# Input_circuits_Page_1.net
KiCad netlist of a schematic drawn in Altium Designer
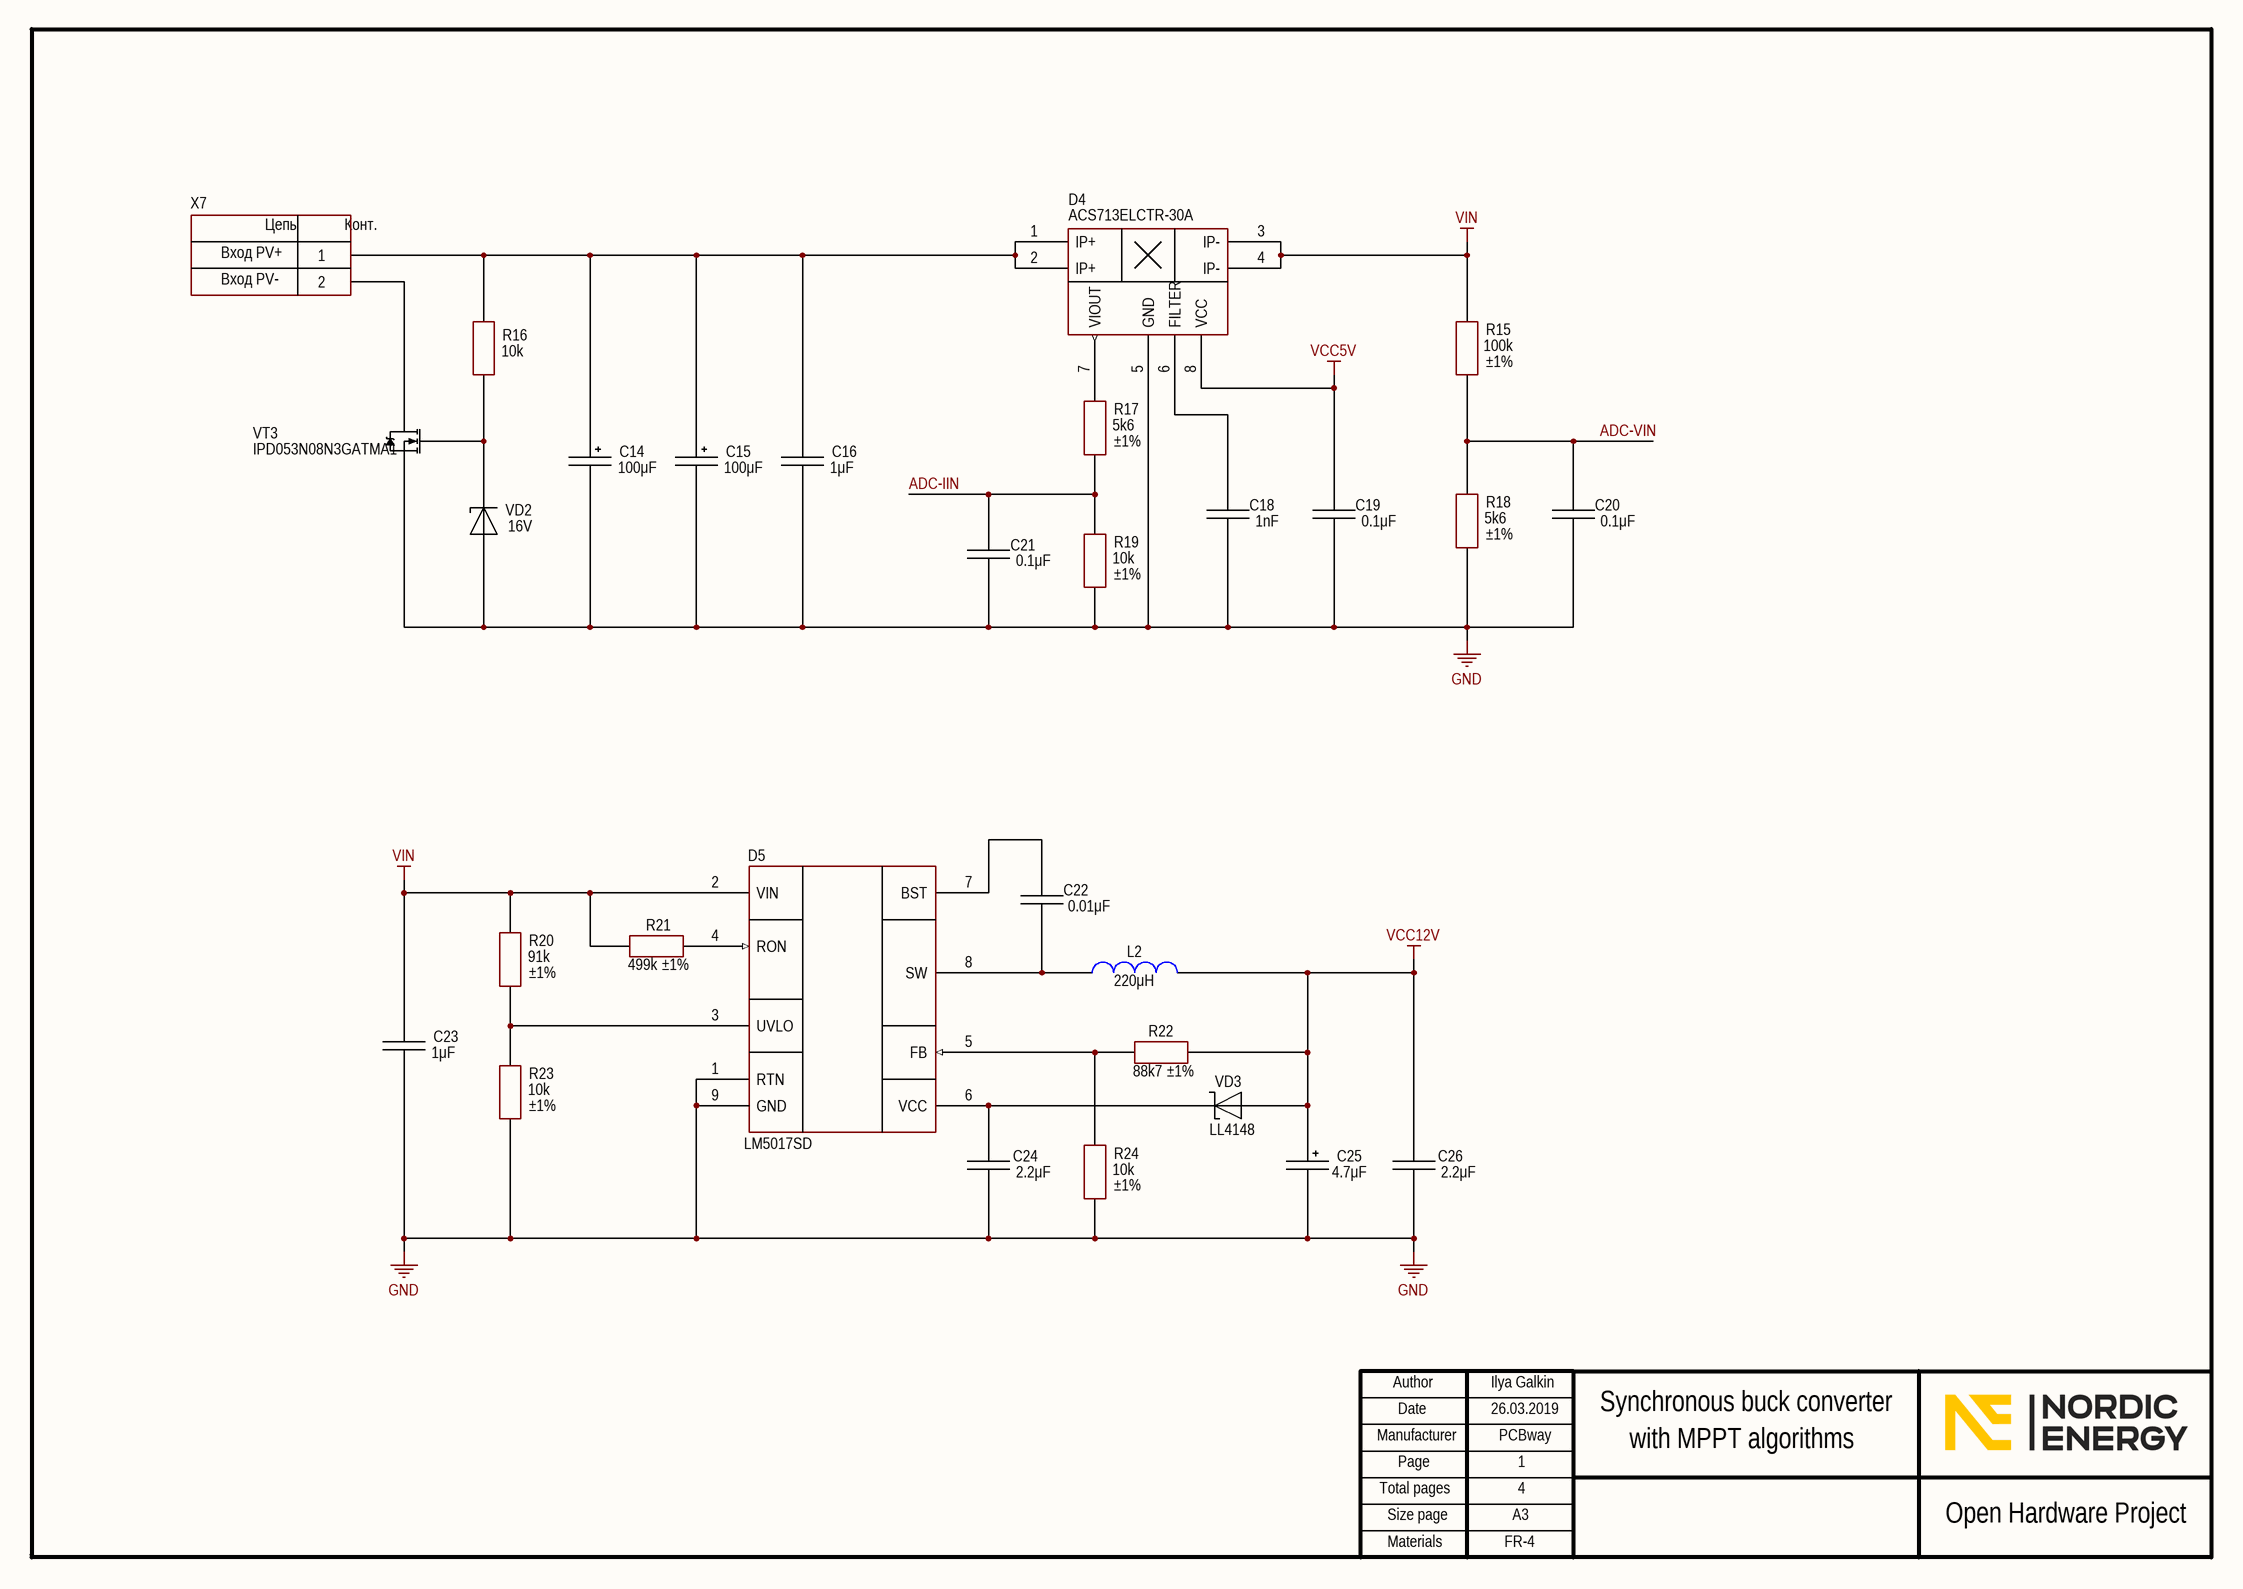
[diagram p0: Input circuits. Page 1.SchDoc]

(export (version "E")
  (design (tool "Eeschema 10.0.6"))
  (components
    (comp (ref "C14")
      (value "100μF")
      (footprint "D10C5H12.5")
      (fields (field (name "MANUFACTURER") "Wurth"))
      (libsource (lib "Discrete") (part "AlumCap"))
    )
    (comp (ref "C15")
      (value "100μF")
      (footprint "D10C5H12.5")
      (fields (field (name "MANUFACTURER") "Wurth"))
      (libsource (lib "Discrete") (part "AlumCap"))
    )
    (comp (ref "C16")
      (value "1μF")
      (footprint "CH1206C")
      (fields (field (name "MANUFACTURER") "Samsung"))
      (libsource (lib "Discrete") (part "Capacitor"))
    )
    (comp (ref "C18")
      (value "1nF")
      (footprint "CH0805C")
      (fields (field (name "MANUFACTURER") "Yageo"))
      (libsource (lib "Discrete") (part "Capacitor"))
    )
    (comp (ref "C19")
      (value "0.1μF")
      (footprint "CH0805C")
      (fields (field (name "MANUFACTURER") "Yageo"))
      (libsource (lib "Discrete") (part "Capacitor"))
    )
    (comp (ref "C20")
      (value "0.1μF")
      (footprint "CH0805C")
      (fields (field (name "MANUFACTURER") "Yageo"))
      (libsource (lib "Discrete") (part "Capacitor"))
    )
    (comp (ref "C21")
      (value "0.1μF")
      (footprint "CH0805C")
      (fields (field (name "MANUFACTURER") "Yageo"))
      (libsource (lib "Discrete") (part "Capacitor"))
    )
    (comp (ref "C22")
      (value "0.01μF")
      (footprint "CH0805C")
      (fields (field (name "MANUFACTURER") "Yageo"))
      (libsource (lib "Discrete") (part "Capacitor"))
    )
    (comp (ref "C23")
      (value "1μF")
      (footprint "CH1206C")
      (fields (field (name "MANUFACTURER") "Samsung"))
      (libsource (lib "Discrete") (part "Capacitor"))
    )
    (comp (ref "C24")
      (value "2.2μF")
      (footprint "CH0805C")
      (fields (field (name "MANUFACTURER") "Yageo"))
      (libsource (lib "Discrete") (part "Capacitor"))
    )
    (comp (ref "C25")
      (value "4.7μF")
      (footprint "TANTAL_B")
      (fields (field (name "MANUFACTURER") "AVX"))
      (libsource (lib "Discrete") (part "TantalCap"))
    )
    (comp (ref "C26")
      (value "2.2μF")
      (footprint "CH0805C")
      (fields (field (name "MANUFACTURER") "Yageo"))
      (libsource (lib "Discrete") (part "Capacitor"))
    )
    (comp (ref "D4")
      (value "ACS713ELCTR-30A")
      (footprint "8-SOIC")
      (description "Sensor")
      (fields (field (name "MANUFACTURER") "Allegro MicroSystems, LLC"))
      (libsource (lib "Power Supplies") (part "ACS713ELCTR-30A-T"))
    )
    (comp (ref "D5")
      (value "LM5017SD")
      (footprint "8-WDFN (4x4 mm)")
      (description "Step-down")
      (fields (field (name "MANUFACTURER") "Texas Instruments"))
      (libsource (lib "Power Supplies") (part "LM5017SD"))
    )
    (comp (ref "L2")
      (value "220μH")
      (footprint "IND: SDR0805")
      (fields (field (name "MANUFACTURER") "Bourns"))
      (libsource (lib "Discrete") (part "Inductor"))
    )
    (comp (ref "R15")
      (value "100k")
      (footprint "CH0805R")
      (fields (field (name "MANUFACTURER") "Yageo") (field (name "COMPONENTKIND") "±1%"))
      (libsource (lib "") (part "Resistor_1"))
    )
    (comp (ref "R16")
      (value "10k")
      (footprint "CH0805R")
      (fields (field (name "MANUFACTURER") "Yageo"))
      (libsource (lib "") (part "Resistor_1"))
    )
    (comp (ref "R17")
      (value "5k6")
      (footprint "CH0805R")
      (fields (field (name "MANUFACTURER") "Yageo") (field (name "COMPONENTKIND") "±1%"))
      (libsource (lib "") (part "Resistor_1"))
    )
    (comp (ref "R18")
      (value "5k6")
      (footprint "CH0805R")
      (fields (field (name "MANUFACTURER") "Yageo") (field (name "COMPONENTKIND") "±1%"))
      (libsource (lib "") (part "Resistor_1"))
    )
    (comp (ref "R19")
      (value "10k")
      (footprint "CH0805R")
      (fields (field (name "MANUFACTURER") "Yageo") (field (name "COMPONENTKIND") "±1%"))
      (libsource (lib "") (part "Resistor_1"))
    )
    (comp (ref "R20")
      (value "91k")
      (footprint "CH0805R")
      (fields (field (name "MANUFACTURER") "Yageo") (field (name "COMPONENTKIND") "±1%"))
      (libsource (lib "") (part "Resistor_1"))
    )
    (comp (ref "R21")
      (value "499k")
      (footprint "CH0805R")
      (fields (field (name "MANUFACTURER") "Yageo") (field (name "COMPONENTKIND") "±1%"))
      (libsource (lib "Discrete") (part "Resistor"))
    )
    (comp (ref "R22")
      (value "88k7")
      (footprint "CH0805R")
      (fields (field (name "MANUFACTURER") "Yageo") (field (name "COMPONENTKIND") "±1%"))
      (libsource (lib "Discrete") (part "Resistor"))
    )
    (comp (ref "R23")
      (value "10k")
      (footprint "CH0805R")
      (fields (field (name "MANUFACTURER") "Yageo") (field (name "COMPONENTKIND") "±1%"))
      (libsource (lib "") (part "Resistor_1"))
    )
    (comp (ref "R24")
      (value "10k")
      (footprint "CH0805R")
      (fields (field (name "MANUFACTURER") "Yageo") (field (name "COMPONENTKIND") "±1%"))
      (libsource (lib "") (part "Resistor_1"))
    )
    (comp (ref "VD2")
      (value "16V")
      (footprint "SOD80")
      (fields (field (name "MANUFACTURER") "Central Semiconductor"))
      (libsource (lib "Diods") (part "Diod Zener"))
    )
    (comp (ref "VD3")
      (value "LL4148")
      (footprint "SOD80")
      (fields (field (name "MANUFACTURER") "ON Semiconductor"))
      (libsource (lib "Diods") (part "Diod Schottky"))
    )
    (comp (ref "VT3")
      (value "IPD053N08N3GATMA1")
      (footprint "D2PAK")
      (description "Mosfet")
      (fields (field (name "MANUFACTURER") "Infineon"))
      (libsource (lib "Transistor") (part "N-chanel"))
    )
    (comp (ref "X7")
      (value "6PCV-02-006")
      (footprint "CON: 6PCV-02-006")
      (fields (field (name "MANUFACTURER") "TE Connectivity"))
      (libsource (lib "Connectors") (part "2-Connector"))
    )
  )
  (nets
    (net (code "1") (name "/ADC-IIN") (class "Default")
      (node (ref "C21") (pin "2") (pinfunction "2_2") (pintype "power_in"))
      (node (ref "R17") (pin "1") (pinfunction "1_1") (pintype "passive"))
      (node (ref "R19") (pin "2") (pinfunction "2_2") (pintype "passive"))
    )
    (net (code "2") (name "/ADC-VIN") (class "Default")
      (node (ref "C20") (pin "2") (pinfunction "2_2") (pintype "power_in"))
      (node (ref "R15") (pin "1") (pinfunction "1_1") (pintype "passive"))
      (node (ref "R18") (pin "2") (pinfunction "2_2") (pintype "passive"))
    )
    (net (code "3") (name "GND") (class "Default")
      (node (ref "C14") (pin "2") (pinfunction "2_2") (pintype "power_in"))
      (node (ref "C15") (pin "2") (pinfunction "2_2") (pintype "power_in"))
      (node (ref "C16") (pin "2") (pinfunction "2_2") (pintype "power_in"))
      (node (ref "C18") (pin "1") (pinfunction "1_1") (pintype "power_in"))
      (node (ref "C19") (pin "1") (pinfunction "1_1") (pintype "power_in"))
      (node (ref "C20") (pin "1") (pinfunction "1_1") (pintype "power_in"))
      (node (ref "C21") (pin "1") (pinfunction "1_1") (pintype "power_in"))
      (node (ref "C23") (pin "2") (pinfunction "2_2") (pintype "power_in"))
      (node (ref "C24") (pin "1") (pinfunction "1_1") (pintype "power_in"))
      (node (ref "C25") (pin "2") (pinfunction "2_2") (pintype "power_in"))
      (node (ref "C26") (pin "1") (pinfunction "1_1") (pintype "power_in"))
      (node (ref "D4") (pin "5") (pinfunction "GND_5") (pintype "passive"))
      (node (ref "D5") (pin "1") (pinfunction "RTN_1") (pintype "passive"))
      (node (ref "D5") (pin "9") (pinfunction "GND_9") (pintype "passive"))
      (node (ref "R18") (pin "1") (pinfunction "1_1") (pintype "passive"))
      (node (ref "R19") (pin "1") (pinfunction "1_1") (pintype "passive"))
      (node (ref "R23") (pin "1") (pinfunction "1_1") (pintype "passive"))
      (node (ref "R24") (pin "1") (pinfunction "1_1") (pintype "passive"))
      (node (ref "VD2") (pin "1") (pinfunction "A_1") (pintype "passive"))
      (node (ref "VT3") (pin "3") (pinfunction "S_3") (pintype "passive"))
    )
    (net (code "4") (name "Net-(C14-Pad1)") (class "Default")
      (node (ref "C14") (pin "1") (pinfunction "1_1") (pintype "power_in"))
      (node (ref "C15") (pin "1") (pinfunction "1_1") (pintype "power_in"))
      (node (ref "C16") (pin "1") (pinfunction "1_1") (pintype "power_in"))
      (node (ref "D4") (pin "1") (pinfunction "IP+_1") (pintype "passive"))
      (node (ref "D4") (pin "2") (pinfunction "IP+_2") (pintype "passive"))
      (node (ref "R16") (pin "2") (pinfunction "2_2") (pintype "passive"))
      (node (ref "X7") (pin "1") (pinfunction "1_1") (pintype "passive"))
    )
    (net (code "5") (name "Net-(D4-FILTER)") (class "Default")
      (node (ref "C18") (pin "2") (pinfunction "2_2") (pintype "power_in"))
      (node (ref "D4") (pin "6") (pinfunction "FILTER_6") (pintype "passive"))
    )
    (net (code "6") (name "Net-(D4-VIOUT)") (class "Default")
      (node (ref "D4") (pin "7") (pinfunction "VIOUT_7") (pintype "output"))
      (node (ref "R17") (pin "2") (pinfunction "2_2") (pintype "passive"))
    )
    (net (code "7") (name "Net-(D5-BST)") (class "Default")
      (node (ref "C22") (pin "2") (pinfunction "2_2") (pintype "power_in"))
      (node (ref "D5") (pin "7") (pinfunction "BST_7") (pintype "passive"))
    )
    (net (code "8") (name "Net-(D5-FB)") (class "Default")
      (node (ref "D5") (pin "5") (pinfunction "FB_5") (pintype "input"))
      (node (ref "R22") (pin "2") (pinfunction "2_2") (pintype "passive"))
      (node (ref "R24") (pin "2") (pinfunction "2_2") (pintype "passive"))
    )
    (net (code "9") (name "Net-(D5-RON)") (class "Default")
      (node (ref "D5") (pin "4") (pinfunction "RON_4") (pintype "input"))
      (node (ref "R21") (pin "1") (pinfunction "1_1") (pintype "passive"))
    )
    (net (code "10") (name "Net-(D5-SW)") (class "Default")
      (node (ref "C22") (pin "1") (pinfunction "1_1") (pintype "power_in"))
      (node (ref "D5") (pin "8") (pinfunction "SW_8") (pintype "passive"))
      (node (ref "L2") (pin "2") (pinfunction "2_2") (pintype "passive"))
    )
    (net (code "11") (name "Net-(D5-UVLO)") (class "Default")
      (node (ref "D5") (pin "3") (pinfunction "UVLO_3") (pintype "passive"))
      (node (ref "R20") (pin "1") (pinfunction "1_1") (pintype "passive"))
      (node (ref "R23") (pin "2") (pinfunction "2_2") (pintype "passive"))
    )
    (net (code "12") (name "Net-(D5-VCC)") (class "Default")
      (node (ref "C24") (pin "2") (pinfunction "2_2") (pintype "power_in"))
      (node (ref "D5") (pin "6") (pinfunction "VCC_6") (pintype "passive"))
      (node (ref "VD3") (pin "2") (pinfunction "2_2") (pintype "passive"))
    )
    (net (code "13") (name "Net-(VD2-C)") (class "Default")
      (node (ref "R16") (pin "1") (pinfunction "1_1") (pintype "passive"))
      (node (ref "VD2") (pin "2") (pinfunction "C_2") (pintype "passive"))
      (node (ref "VT3") (pin "1") (pinfunction "G_1") (pintype "passive"))
    )
    (net (code "14") (name "Net-(VT3-D)") (class "Default")
      (node (ref "VT3") (pin "2") (pinfunction "D_2") (pintype "passive"))
      (node (ref "X7") (pin "2") (pinfunction "2_2") (pintype "passive"))
    )
    (net (code "15") (name "VCC5V") (class "Default")
      (node (ref "C19") (pin "2") (pinfunction "2_2") (pintype "power_in"))
      (node (ref "D4") (pin "8") (pinfunction "VCC_8") (pintype "passive"))
    )
    (net (code "16") (name "VCC12V") (class "Default")
      (node (ref "C25") (pin "1") (pinfunction "1_1") (pintype "power_in"))
      (node (ref "C26") (pin "2") (pinfunction "2_2") (pintype "power_in"))
      (node (ref "L2") (pin "1") (pinfunction "1_1") (pintype "passive"))
      (node (ref "R22") (pin "1") (pinfunction "1_1") (pintype "passive"))
      (node (ref "VD3") (pin "1") (pinfunction "1_1") (pintype "passive"))
    )
    (net (code "17") (name "VIN") (class "Default")
      (node (ref "C23") (pin "1") (pinfunction "1_1") (pintype "power_in"))
      (node (ref "D4") (pin "3") (pinfunction "IP-_3") (pintype "passive"))
      (node (ref "D4") (pin "4") (pinfunction "IP-_4") (pintype "passive"))
      (node (ref "D5") (pin "2") (pinfunction "VIN_2") (pintype "passive"))
      (node (ref "R15") (pin "2") (pinfunction "2_2") (pintype "passive"))
      (node (ref "R20") (pin "2") (pinfunction "2_2") (pintype "passive"))
      (node (ref "R21") (pin "2") (pinfunction "2_2") (pintype "passive"))
    )
  )
)
